# TFT.net
KiCad netlist of a schematic drawn in Altium Designer
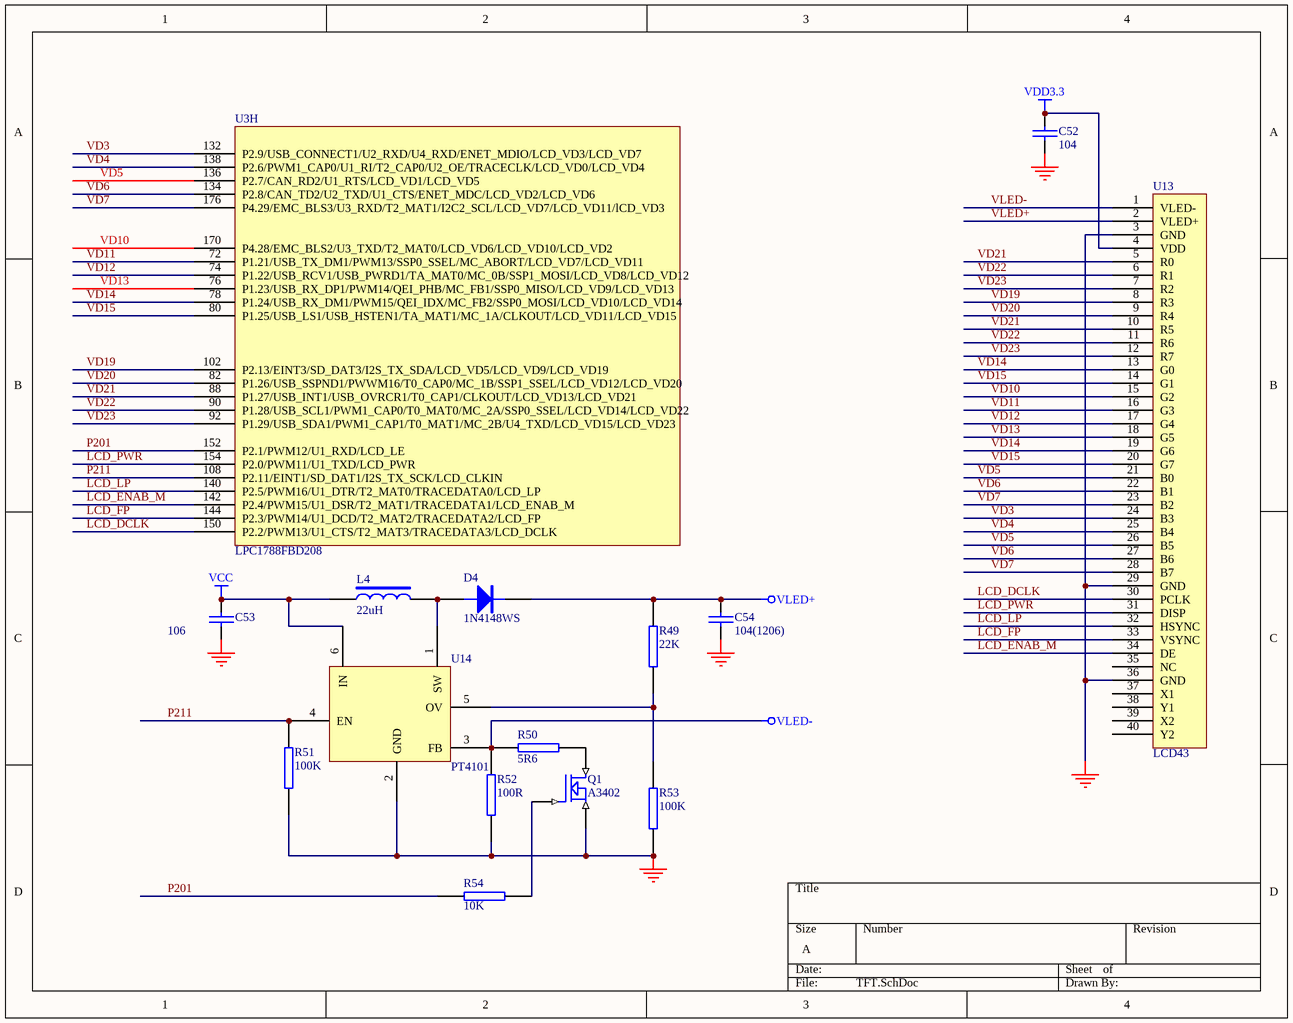
[diagram p0: TFT.SchDoc]

(export (version "E")
  (design (tool "Eeschema 10.0.6"))
  (components
    (comp (ref "C52")
      (value "104")
      (footprint "C0603")
      (description "Capacitor")
      (libsource (lib "*") (part "CAP"))
    )
    (comp (ref "C53")
      (value "106")
      (footprint "C0805")
      (description "Capacitor")
      (libsource (lib "*") (part "CAP"))
    )
    (comp (ref "C54")
      (value "104(1206)")
      (footprint "C1206")
      (description "Capacitor")
      (libsource (lib "*") (part "CAP"))
    )
    (comp (ref "D4")
      (value "1N4148WS")
      (footprint "SOD323")
      (description "Diode")
      (libsource (lib "*") (part "DIODE"))
    )
    (comp (ref "L4") (value "22uH") (footprint "L4X4") (libsource (lib "*") (part "INDUCTOR2")))
    (comp (ref "Q1") (value "A3402") (footprint "SOT23_9013") (libsource (lib "*") (part "MOSFET N")))
    (comp (ref "R49") (value "22K") (footprint "R0603") (libsource (lib "*") (part "RES2")))
    (comp (ref "R50") (value "5R6") (footprint "R0603") (libsource (lib "*") (part "RES2")))
    (comp (ref "R51") (value "100K") (footprint "R0603") (libsource (lib "*") (part "RES2")))
    (comp (ref "R52") (value "100R") (footprint "R0603") (libsource (lib "*") (part "RES2")))
    (comp (ref "R53") (value "100K") (footprint "R0603") (libsource (lib "*") (part "RES2")))
    (comp (ref "R54") (value "10K") (footprint "R0603") (libsource (lib "*") (part "RES2")))
    (comp (ref "U3")
      (value "LPC1788FBD208")
      (footprint "QFP208")
      (libsource (lib "LPC1788") (part "LPC1788FBD208"))
    )
    (comp (ref "U13") (value "LCD43") (footprint "SMTSOFT40") (libsource (lib "*") (part "LCD43")))
    (comp (ref "U14") (value "PT4101") (footprint "SOT23-6") (libsource (lib "*") (part "PT4101")))
  )
  (nets
    (net (code "1") (name "/LCD_DCLK") (class "Default")
      (node (ref "U13") (pin "30") (pinfunction "PCLK_30") (pintype "passive"))
      (node (ref "U3") (pin "150") (pinfunction "P2.2/PWM13/U1_CTS/T2_MAT3/TRACEDATA3/LCD_DCLK_150") (pintype "passive"))
    )
    (net (code "2") (name "/LCD_ENAB_M") (class "Default")
      (node (ref "U13") (pin "34") (pinfunction "DE_34") (pintype "passive"))
      (node (ref "U3") (pin "142") (pinfunction "P2.4/PWM15/U1_DSR/T2_MAT1/TRACEDATA1/LCD_ENAB_M_142") (pintype "passive"))
    )
    (net (code "3") (name "/LCD_FP") (class "Default")
      (node (ref "U13") (pin "33") (pinfunction "VSYNC_33") (pintype "passive"))
      (node (ref "U3") (pin "144") (pinfunction "P2.3/PWM14/U1_DCD/T2_MAT2/TRACEDATA2/LCD_FP_144") (pintype "passive"))
    )
    (net (code "4") (name "/LCD_LP") (class "Default")
      (node (ref "U13") (pin "32") (pinfunction "HSYNC_32") (pintype "passive"))
      (node (ref "U3") (pin "140") (pinfunction "P2.5/PWM16/U1_DTR/T2_MAT0/TRACEDATA0/LCD_LP_140") (pintype "passive"))
    )
    (net (code "5") (name "/LCD_PWR") (class "Default")
      (node (ref "U13") (pin "31") (pinfunction "DISP_31") (pintype "passive"))
      (node (ref "U3") (pin "154") (pinfunction "P2.0/PWM11/U1_TXD/LCD_PWR_154") (pintype "passive"))
    )
    (net (code "6") (name "/P201") (class "Default")
      (node (ref "R54") (pin "1") (pinfunction "1_1") (pintype "passive"))
      (node (ref "U3") (pin "152") (pinfunction "P2.1/PWM12/U1_RXD/LCD_LE_152") (pintype "passive"))
    )
    (net (code "7") (name "/P211") (class "Default")
      (node (ref "R51") (pin "1") (pinfunction "1_1") (pintype "passive"))
      (node (ref "U14") (pin "4") (pinfunction "EN_4") (pintype "passive"))
      (node (ref "U3") (pin "108") (pinfunction "P2.11/EINT1/SD_DAT1/I2S_TX_SCK/LCD_CLKIN_108") (pintype "passive"))
    )
    (net (code "8") (name "/VD3") (class "Default")
      (node (ref "U13") (pin "24") (pinfunction "B3_24") (pintype "passive"))
      (node (ref "U3") (pin "132") (pinfunction "P2.9/USB_CONNECT1/U2_RXD/U4_RXD/ENET_MDIO/LCD_VD3/LCD_VD7_132") (pintype "passive"))
    )
    (net (code "9") (name "/VD4") (class "Default")
      (node (ref "U13") (pin "25") (pinfunction "B4_25") (pintype "passive"))
      (node (ref "U3") (pin "138") (pinfunction "P2.6/PWM1_CAP0/U1_RI/T2_CAP0/U2_OE/TRACECLK/LCD_VD0/LCD_VD4_138") (pintype "passive"))
    )
    (net (code "10") (name "/VD5") (class "Default")
      (node (ref "U13") (pin "21") (pinfunction "B0_21") (pintype "passive"))
      (node (ref "U13") (pin "26") (pinfunction "B5_26") (pintype "passive"))
      (node (ref "U3") (pin "136") (pinfunction "P2.7/CAN_RD2/U1_RTS/LCD_VD1/LCD_VD5_136") (pintype "passive"))
    )
    (net (code "11") (name "/VD6") (class "Default")
      (node (ref "U13") (pin "22") (pinfunction "B1_22") (pintype "passive"))
      (node (ref "U13") (pin "27") (pinfunction "B6_27") (pintype "passive"))
      (node (ref "U3") (pin "134") (pinfunction "P2.8/CAN_TD2/U2_TXD/U1_CTS/ENET_MDC/LCD_VD2/LCD_VD6_134") (pintype "passive"))
    )
    (net (code "12") (name "/VD7") (class "Default")
      (node (ref "U13") (pin "23") (pinfunction "B2_23") (pintype "passive"))
      (node (ref "U13") (pin "28") (pinfunction "B7_28") (pintype "passive"))
      (node (ref "U3") (pin "176") (pinfunction "P4.29/EMC_BLS3/U3_RXD/T2_MAT1/I2C2_SCL/LCD_VD7/LCD_VD11/lCD_VD3_176") (pintype "passive"))
    )
    (net (code "13") (name "/VD10") (class "Default")
      (node (ref "U13") (pin "15") (pinfunction "G2_15") (pintype "passive"))
      (node (ref "U3") (pin "170") (pinfunction "P4.28/EMC_BLS2/U3_TXD/T2_MAT0/LCD_VD6/LCD_VD10/LCD_VD2_170") (pintype "passive"))
    )
    (net (code "14") (name "/VD11") (class "Default")
      (node (ref "U13") (pin "16") (pinfunction "G3_16") (pintype "passive"))
      (node (ref "U3") (pin "72") (pinfunction "P1.21/USB_TX_DM1/PWM13/SSP0_SSEL/MC_ABORT/LCD_VD7/LCD_VD11_72") (pintype "passive"))
    )
    (net (code "15") (name "/VD12") (class "Default")
      (node (ref "U13") (pin "17") (pinfunction "G4_17") (pintype "passive"))
      (node (ref "U3") (pin "74") (pinfunction "P1.22/USB_RCV1/USB_PWRD1/TA_MAT0/MC_0B/SSP1_MOSI/LCD_VD8/LCD_VD12_74") (pintype "passive"))
    )
    (net (code "16") (name "/VD13") (class "Default")
      (node (ref "U13") (pin "18") (pinfunction "G5_18") (pintype "passive"))
      (node (ref "U3") (pin "76") (pinfunction "P1.23/USB_RX_DP1/PWM14/QEI_PHB/MC_FB1/SSP0_MISO/LCD_VD9/LCD_VD13_76") (pintype "passive"))
    )
    (net (code "17") (name "/VD14") (class "Default")
      (node (ref "U13") (pin "13") (pinfunction "G0_13") (pintype "passive"))
      (node (ref "U13") (pin "19") (pinfunction "G6_19") (pintype "passive"))
      (node (ref "U3") (pin "78") (pinfunction "P1.24/USB_RX_DM1/PWM15/QEI_IDX/MC_FB2/SSP0_MOSI/LCD_VD10/LCD_VD14_78") (pintype "passive"))
    )
    (net (code "18") (name "/VD15") (class "Default")
      (node (ref "U13") (pin "14") (pinfunction "G1_14") (pintype "passive"))
      (node (ref "U13") (pin "20") (pinfunction "G7_20") (pintype "passive"))
      (node (ref "U3") (pin "80") (pinfunction "P1.25/USB_LS1/USB_HSTEN1/TA_MAT1/MC_1A/CLKOUT/LCD_VD11/LCD_VD15_80") (pintype "passive"))
    )
    (net (code "19") (name "/VD19") (class "Default")
      (node (ref "U13") (pin "8") (pinfunction "R3_8") (pintype "passive"))
      (node (ref "U3") (pin "102") (pinfunction "P2.13/EINT3/SD_DAT3/I2S_TX_SDA/LCD_VD5/LCD_VD9/LCD_VD19_102") (pintype "passive"))
    )
    (net (code "20") (name "/VD20") (class "Default")
      (node (ref "U13") (pin "9") (pinfunction "R4_9") (pintype "passive"))
      (node (ref "U3") (pin "82") (pinfunction "P1.26/USB_SSPND1/PWWM16/T0_CAP0/MC_1B/SSP1_SSEL/LCD_VD12/LCD_VD20_82") (pintype "passive"))
    )
    (net (code "21") (name "/VD21") (class "Default")
      (node (ref "U13") (pin "10") (pinfunction "R5_10") (pintype "passive"))
      (node (ref "U13") (pin "5") (pinfunction "R0_5") (pintype "passive"))
      (node (ref "U3") (pin "88") (pinfunction "P1.27/USB_INT1/USB_OVRCR1/T0_CAP1/CLKOUT/LCD_VD13/LCD_VD21_88") (pintype "passive"))
    )
    (net (code "22") (name "/VD22") (class "Default")
      (node (ref "U13") (pin "11") (pinfunction "R6_11") (pintype "passive"))
      (node (ref "U13") (pin "6") (pinfunction "R1_6") (pintype "passive"))
      (node (ref "U3") (pin "90") (pinfunction "P1.28/USB_SCL1/PWM1_CAP0/T0_MAT0/MC_2A/SSP0_SSEL/LCD_VD14/LCD_VD22_90") (pintype "passive"))
    )
    (net (code "23") (name "/VD23") (class "Default")
      (node (ref "U13") (pin "12") (pinfunction "R7_12") (pintype "passive"))
      (node (ref "U13") (pin "7") (pinfunction "R2_7") (pintype "passive"))
      (node (ref "U3") (pin "92") (pinfunction "P1.29/USB_SDA1/PWM1_CAP1/T0_MAT1/MC_2B/U4_TXD/LCD_VD15/LCD_VD23_92") (pintype "passive"))
    )
    (net (code "24") (name "GND") (class "Default")
      (node (ref "C52") (pin "2") (pinfunction "2_2") (pintype "passive"))
      (node (ref "C53") (pin "2") (pinfunction "2_2") (pintype "passive"))
      (node (ref "C54") (pin "2") (pinfunction "2_2") (pintype "passive"))
      (node (ref "Q1") (pin "3") (pinfunction "S_3") (pintype "input"))
      (node (ref "R51") (pin "2") (pinfunction "2_2") (pintype "passive"))
      (node (ref "R52") (pin "2") (pinfunction "2_2") (pintype "passive"))
      (node (ref "R53") (pin "1") (pinfunction "1_1") (pintype "passive"))
      (node (ref "U13") (pin "29") (pinfunction "GND_29") (pintype "passive"))
      (node (ref "U13") (pin "3") (pinfunction "GND_3") (pintype "passive"))
      (node (ref "U13") (pin "36") (pinfunction "GND_36") (pintype "passive"))
      (node (ref "U14") (pin "2") (pinfunction "GND_2") (pintype "passive"))
    )
    (net (code "25") (name "Net-(D4-A)") (class "Default")
      (node (ref "D4") (pin "1") (pinfunction "A_1") (pintype "passive"))
      (node (ref "L4") (pin "2") (pinfunction "2_2") (pintype "passive"))
      (node (ref "U14") (pin "1") (pinfunction "SW_1") (pintype "passive"))
    )
    (net (code "26") (name "Net-(Q1-D)") (class "Default")
      (node (ref "Q1") (pin "2") (pinfunction "D_2") (pintype "input"))
      (node (ref "R50") (pin "1") (pinfunction "1_1") (pintype "passive"))
    )
    (net (code "27") (name "Net-(Q1-G)") (class "Default")
      (node (ref "Q1") (pin "1") (pinfunction "G_1") (pintype "input"))
      (node (ref "R54") (pin "2") (pinfunction "2_2") (pintype "passive"))
    )
    (net (code "28") (name "Net-(U14-OV)") (class "Default")
      (node (ref "R49") (pin "1") (pinfunction "1_1") (pintype "passive"))
      (node (ref "R53") (pin "2") (pinfunction "2_2") (pintype "passive"))
      (node (ref "U14") (pin "5") (pinfunction "OV_5") (pintype "passive"))
    )
    (net (code "29") (name "VCC") (class "Default")
      (node (ref "C53") (pin "1") (pinfunction "1_1") (pintype "passive"))
      (node (ref "L4") (pin "1") (pinfunction "1_1") (pintype "passive"))
      (node (ref "U14") (pin "6") (pinfunction "IN_6") (pintype "passive"))
    )
    (net (code "30") (name "VDD3.3") (class "Default")
      (node (ref "C52") (pin "1") (pinfunction "1_1") (pintype "passive"))
      (node (ref "U13") (pin "4") (pinfunction "VDD_4") (pintype "passive"))
    )
    (net (code "31") (name "VLED+") (class "Default")
      (node (ref "C54") (pin "1") (pinfunction "1_1") (pintype "passive"))
      (node (ref "D4") (pin "2") (pinfunction "K_2") (pintype "passive"))
      (node (ref "R49") (pin "2") (pinfunction "2_2") (pintype "passive"))
      (node (ref "U13") (pin "2") (pinfunction "VLED+_2") (pintype "passive"))
    )
    (net (code "32") (name "VLED-") (class "Default")
      (node (ref "R50") (pin "2") (pinfunction "2_2") (pintype "passive"))
      (node (ref "R52") (pin "1") (pinfunction "1_1") (pintype "passive"))
      (node (ref "U13") (pin "1") (pinfunction "VLED-_1") (pintype "passive"))
      (node (ref "U14") (pin "3") (pinfunction "FB_3") (pintype "passive"))
    )
    (net (code "33") (name "unconnected-(U13-NC-Pad35)") (class "Default")
      (node (ref "U13") (pin "35") (pinfunction "NC_35") (pintype "passive"))
    )
    (net (code "34") (name "unconnected-(U13-X1-Pad37)") (class "Default")
      (node (ref "U13") (pin "37") (pinfunction "X1_37") (pintype "passive"))
    )
    (net (code "35") (name "unconnected-(U13-X2-Pad39)") (class "Default")
      (node (ref "U13") (pin "39") (pinfunction "X2_39") (pintype "passive"))
    )
    (net (code "36") (name "unconnected-(U13-Y1-Pad38)") (class "Default")
      (node (ref "U13") (pin "38") (pinfunction "Y1_38") (pintype "passive"))
    )
    (net (code "37") (name "unconnected-(U13-Y2-Pad40)") (class "Default")
      (node (ref "U13") (pin "40") (pinfunction "Y2_40") (pintype "passive"))
    )
  )
)
